# Block_Diagram.net
KiCad netlist of a schematic drawn in Altium Designer
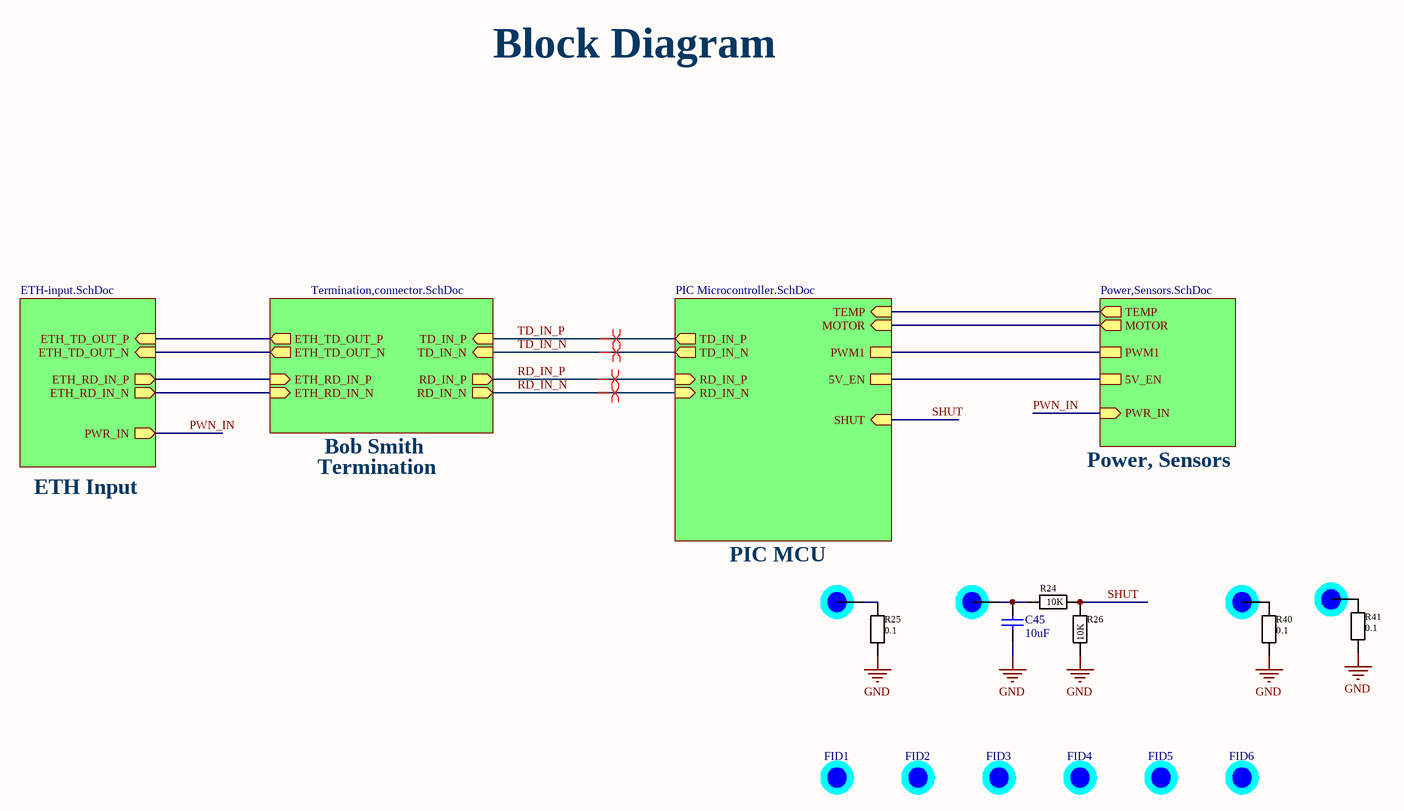
[diagram p0: Block Diagram.SchDoc]

(export (version "E")
  (design (tool "Eeschema 10.0.6"))
  (components
    (comp (ref "C45")
      (value "10uF")
      (footprint "CAPC1005X61USR")
      (description "CAP CER 10UF 10V X5R 0402")
      (fields
        (field (name "MANUFACTURER") "Samsung Electro-Mechanics")
        (field (name "MANUFACTURER PART NUMBER") "CL05A106MP8NUB8")
      )
      (libsource (lib "8-port switch") (part "Cap"))
    )
    (comp (ref "FID1")
      (value "Fiducial 1mm")
      (footprint "FIDUCIAL_1MM_RND")
      (libsource (lib "Cam Card V1") (part "FIDUCIAL_1MM_RND"))
    )
    (comp (ref "FID2")
      (value "Fiducial 1mm")
      (footprint "FIDUCIAL_1MM_RND")
      (libsource (lib "Cam Card V1") (part "FIDUCIAL_1MM_RND"))
    )
    (comp (ref "FID3")
      (value "Fiducial 1mm")
      (footprint "FIDUCIAL_1MM_RND")
      (libsource (lib "Cam Card V1") (part "FIDUCIAL_1MM_RND"))
    )
    (comp (ref "FID4")
      (value "Fiducial 1mm")
      (footprint "FIDUCIAL_1MM_RND")
      (libsource (lib "Cam Card V1") (part "FIDUCIAL_1MM_RND"))
    )
    (comp (ref "FID5")
      (value "Fiducial 1mm")
      (footprint "FIDUCIAL_1MM_RND")
      (libsource (lib "Cam Card V1") (part "FIDUCIAL_1MM_RND"))
    )
    (comp (ref "FID6")
      (value "Fiducial 1mm")
      (footprint "FIDUCIAL_1MM_RND")
      (libsource (lib "Cam Card V1") (part "FIDUCIAL_1MM_RND"))
    )
    (comp (ref "MH1")
      (value "MH_1.5mm")
      (footprint "MH_2mm")
      (libsource (lib "Cam Card V1") (part "MH_1.5mm"))
    )
    (comp (ref "MH2")
      (value "MH_1.5mm")
      (footprint "MH_2mm")
      (libsource (lib "Cam Card V1") (part "MH_1.5mm"))
    )
    (comp (ref "MH3")
      (value "MH_1.5mm")
      (footprint "MH_2mm")
      (libsource (lib "Cam Card V1") (part "MH_1.5mm"))
    )
    (comp (ref "MH4")
      (value "MH_1.5mm")
      (footprint "MH_2mm")
      (libsource (lib "Cam Card V1") (part "MH_1.5mm"))
    )
    (comp (ref "R24")
      (value "10K")
      (footprint "RESC1005X40USR")
      (description "RES 10K OHM 1% 1/16W 0402")
      (fields
        (field (name "MANUFACTURER") "Stackpole Electronics Inc")
        (field (name "MANUFACTURER PART NUMBER") "RMCF0402FT10K0")
      )
      (libsource (lib "") (part "R_1"))
    )
    (comp (ref "R25")
      (value "0.1")
      (footprint "RESC2012X65USR")
      (description "RES 0.1 OHM 1% 1/8W 0805")
      (fields
        (field (name "MANUFACTURER") "Yageo")
        (field (name "MANUFACTURER PART NUMBER") "RL0805FR-070R1L")
      )
      (libsource (lib "26-port switch") (part "R"))
    )
    (comp (ref "R26")
      (value "10K")
      (footprint "RESC1005X40USR")
      (description "RES 10K OHM 1% 1/16W 0402")
      (fields
        (field (name "MANUFACTURER") "Stackpole Electronics Inc")
        (field (name "MANUFACTURER PART NUMBER") "RMCF0402FT10K0")
      )
      (libsource (lib "") (part "R_2"))
    )
    (comp (ref "R40")
      (value "0.1")
      (footprint "RESC2012X65USR")
      (description "RES 0.1 OHM 1% 1/8W 0805")
      (fields
        (field (name "MANUFACTURER") "Yageo")
        (field (name "MANUFACTURER PART NUMBER") "RL0805FR-070R1L")
      )
      (libsource (lib "26-port switch") (part "R"))
    )
    (comp (ref "R41")
      (value "0.1")
      (footprint "RESC2012X65USR")
      (description "RES 0.1 OHM 1% 1/8W 0805")
      (fields
        (field (name "MANUFACTURER") "Yageo")
        (field (name "MANUFACTURER PART NUMBER") "RL0805FR-070R1L")
      )
      (libsource (lib "26-port switch") (part "R"))
    )
  )
  (nets
    (net (code "11") (name "/SHUT") (class "Default")
      (node (ref "R24") (pin "2") (pintype "passive"))
      (node (ref "R26") (pin "1") (pintype "passive"))
    )
    (net (code "15") (name "GND") (class "Default")
      (node (ref "C45") (pin "2") (pinfunction "2_2") (pintype "passive"))
      (node (ref "R25") (pin "1") (pintype "passive"))
      (node (ref "R26") (pin "2") (pintype "passive"))
      (node (ref "R40") (pin "1") (pintype "passive"))
      (node (ref "R41") (pin "1") (pintype "passive"))
    )
    (net (code "16") (name "Net-(C45-Pad1)") (class "Default")
      (node (ref "C45") (pin "1") (pinfunction "1_1") (pintype "passive"))
      (node (ref "MH2") (pin "1") (pinfunction "1_1") (pintype "passive"))
      (node (ref "R24") (pin "1") (pintype "passive"))
    )
    (net (code "17") (name "Net-(MH1-Pad1)") (class "Default")
      (node (ref "MH1") (pin "1") (pinfunction "1_1") (pintype "passive"))
      (node (ref "R25") (pin "2") (pintype "passive"))
    )
    (net (code "18") (name "Net-(MH3-Pad1)") (class "Default")
      (node (ref "MH3") (pin "1") (pinfunction "1_1") (pintype "passive"))
      (node (ref "R40") (pin "2") (pintype "passive"))
    )
    (net (code "19") (name "Net-(MH4-Pad1)") (class "Default")
      (node (ref "MH4") (pin "1") (pinfunction "1_1") (pintype "passive"))
      (node (ref "R41") (pin "2") (pintype "passive"))
    )
  )
)
